# PM_proto_2.net
KiCad netlist of a schematic drawn in EAGLE
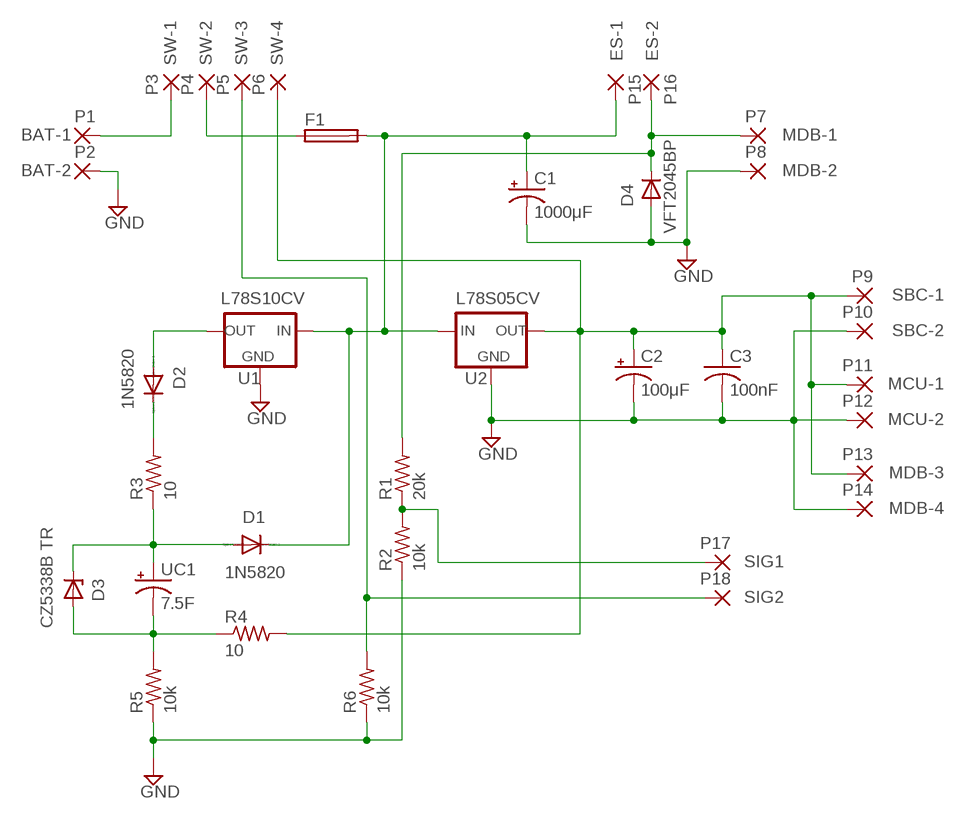
[diagram p0: schematic, sheet 1]

(export (version "E")
  (design (tool "Eeschema 10.0.6"))
  (components
    (comp (ref "C1")
      (value "1000μF")
      (footprint "eagle-import:E7,5-16")
      (libsource (lib "eagle-import") (part "CPOL-USE7.5-16"))
    )
    (comp (ref "C2")
      (value "100μF")
      (footprint "eagle-import:E2,5-6E")
      (libsource (lib "eagle-import") (part "CPOL-USE2,5-6E"))
    )
    (comp (ref "C3")
      (value "100nF")
      (footprint "eagle-import:C050-024X044")
      (libsource (lib "eagle-import") (part "C-US050-024X044"))
    )
    (comp (ref "D1")
      (value "1N5820")
      (footprint "eagle-import:DO41-10")
      (libsource (lib "eagle-import") (part "1N4004"))
    )
    (comp (ref "D2")
      (value "1N5820")
      (footprint "eagle-import:DO41-10")
      (libsource (lib "eagle-import") (part "1N4004"))
    )
    (comp (ref "D3")
      (value "CZ5338B TR")
      (footprint "eagle-import:DO41Z10")
      (libsource (lib "eagle-import") (part "1N4728"))
    )
    (comp (ref "D4")
      (value "VFT2045BP")
      (footprint "eagle-import:VFT2045BP")
      (libsource (lib "eagle-import") (part "VFT2045BP"))
    )
    (comp (ref "F1")
      (value "0297015FUSE")
      (footprint "eagle-import:0297015HOLDER")
      (libsource (lib "eagle-import") (part "0297015FUSE"))
    )
    (comp (ref "P1")
      (value "BAT-1")
      (footprint "eagle-import:1,6_0,8")
      (libsource (lib "eagle-import") (part "1,6/0,8"))
    )
    (comp (ref "P2")
      (value "BAT-2")
      (footprint "eagle-import:1,6_0,8")
      (libsource (lib "eagle-import") (part "1,6/0,8"))
    )
    (comp (ref "P3")
      (value "SW-1")
      (footprint "eagle-import:1,6_0,8")
      (libsource (lib "eagle-import") (part "1,6/0,8"))
    )
    (comp (ref "P4")
      (value "SW-2")
      (footprint "eagle-import:1,6_0,8")
      (libsource (lib "eagle-import") (part "1,6/0,8"))
    )
    (comp (ref "P5")
      (value "SW-3")
      (footprint "eagle-import:1,6_0,8")
      (libsource (lib "eagle-import") (part "1,6/0,8"))
    )
    (comp (ref "P6")
      (value "SW-4")
      (footprint "eagle-import:1,6_0,8")
      (libsource (lib "eagle-import") (part "1,6/0,8"))
    )
    (comp (ref "P7")
      (value "MDB-1")
      (footprint "eagle-import:1,6_0,8")
      (libsource (lib "eagle-import") (part "1,6/0,8"))
    )
    (comp (ref "P8")
      (value "MDB-2")
      (footprint "eagle-import:1,6_0,8")
      (libsource (lib "eagle-import") (part "1,6/0,8"))
    )
    (comp (ref "P9")
      (value "SBC-1")
      (footprint "eagle-import:1,6_0,8")
      (libsource (lib "eagle-import") (part "1,6/0,8"))
    )
    (comp (ref "P10")
      (value "SBC-2")
      (footprint "eagle-import:1,6_0,8")
      (libsource (lib "eagle-import") (part "1,6/0,8"))
    )
    (comp (ref "P11")
      (value "MCU-1")
      (footprint "eagle-import:1,6_0,8")
      (libsource (lib "eagle-import") (part "1,6/0,8"))
    )
    (comp (ref "P12")
      (value "MCU-2")
      (footprint "eagle-import:1,6_0,8")
      (libsource (lib "eagle-import") (part "1,6/0,8"))
    )
    (comp (ref "P13")
      (value "MDB-3")
      (footprint "eagle-import:1,6_0,8")
      (libsource (lib "eagle-import") (part "1,6/0,8"))
    )
    (comp (ref "P14")
      (value "MDB-4")
      (footprint "eagle-import:1,6_0,8")
      (libsource (lib "eagle-import") (part "1,6/0,8"))
    )
    (comp (ref "P15")
      (value "ES-1")
      (footprint "eagle-import:1,6_0,8")
      (libsource (lib "eagle-import") (part "1,6/0,8"))
    )
    (comp (ref "P16")
      (value "ES-2")
      (footprint "eagle-import:1,6_0,8")
      (libsource (lib "eagle-import") (part "1,6/0,8"))
    )
    (comp (ref "P17")
      (value "SIG1")
      (footprint "eagle-import:1,6_0,8")
      (libsource (lib "eagle-import") (part "1,6/0,8"))
    )
    (comp (ref "P18")
      (value "SIG2")
      (footprint "eagle-import:1,6_0,8")
      (libsource (lib "eagle-import") (part "1,6/0,8"))
    )
    (comp (ref "R1")
      (value "20k")
      (footprint "eagle-import:0204_7")
      (libsource (lib "eagle-import") (part "R-US_0204/7"))
    )
    (comp (ref "R2")
      (value "10k")
      (footprint "eagle-import:0204_7")
      (libsource (lib "eagle-import") (part "R-US_0204/7"))
    )
    (comp (ref "R3")
      (value "10")
      (footprint "eagle-import:TNP10SC10R0FE")
      (libsource (lib "eagle-import") (part "TNP10SC10R0FE"))
    )
    (comp (ref "R4")
      (value "10")
      (footprint "eagle-import:TNP10SC10R0FE")
      (libsource (lib "eagle-import") (part "TNP10SC10R0FE"))
    )
    (comp (ref "R5")
      (value "10k")
      (footprint "eagle-import:0204_7")
      (libsource (lib "eagle-import") (part "R-US_0204/7"))
    )
    (comp (ref "R6")
      (value "10k")
      (footprint "eagle-import:0204_7")
      (libsource (lib "eagle-import") (part "R-US_0204/7"))
    )
    (comp (ref "U1")
      (value "L78S10CV")
      (footprint "eagle-import:78XXS")
      (libsource (lib "eagle-import") (part "78XXS"))
    )
    (comp (ref "U2")
      (value "L78S05CV")
      (footprint "eagle-import:78XXS")
      (fields (field (name "SPICEPREFIX") "J"))
      (libsource (lib "eagle-import") (part "78XXS"))
    )
    (comp (ref "UC1")
      (value "7.5F")
      (footprint "eagle-import:SCMT32D755MRBB0")
      (libsource (lib "eagle-import") (part "SCMT32D755MRBB0"))
    )
  )
  (nets
    (net (code "1") (name "GND") (class "Default")
      (node (ref "C1") (pin "-") (pinfunction "-_-") (pintype "passive"))
      (node (ref "C2") (pin "-") (pinfunction "-_-") (pintype "passive"))
      (node (ref "C3") (pin "2") (pinfunction "2_2") (pintype "passive"))
      (node (ref "D4") (pin "2") (pinfunction "A_2") (pintype "passive"))
      (node (ref "P10") (pin "1") (pinfunction "P_1") (pintype "passive"))
      (node (ref "P12") (pin "1") (pinfunction "P_1") (pintype "passive"))
      (node (ref "P14") (pin "1") (pinfunction "P_1") (pintype "passive"))
      (node (ref "P2") (pin "1") (pinfunction "P_1") (pintype "passive"))
      (node (ref "P8") (pin "1") (pinfunction "P_1") (pintype "passive"))
      (node (ref "R2") (pin "1") (pinfunction "1_1") (pintype "passive"))
      (node (ref "R5") (pin "1") (pinfunction "1_1") (pintype "passive"))
      (node (ref "R6") (pin "1") (pinfunction "1_1") (pintype "passive"))
      (node (ref "U1") (pin "GND") (pinfunction "GND_GND") (pintype "input"))
      (node (ref "U2") (pin "GND") (pinfunction "GND_GND") (pintype "input"))
    )
    (net (code "2") (name "Net-(D2-PadA)") (class "Default")
      (node (ref "D2") (pin "A") (pinfunction "A_A") (pintype "passive"))
      (node (ref "U1") (pin "OUT") (pinfunction "OUT_OUT") (pintype "passive"))
    )
    (net (code "3") (name "Net-(D2-PadC)") (class "Default")
      (node (ref "D2") (pin "C") (pinfunction "C_C") (pintype "passive"))
      (node (ref "R3") (pin "2") (pinfunction "2_2") (pintype "passive"))
    )
    (net (code "4") (name "Net-(D4-C)") (class "Default")
      (node (ref "D4") (pin "1") (pinfunction "C_1") (pintype "passive"))
      (node (ref "P16") (pin "1") (pinfunction "P_1") (pintype "passive"))
      (node (ref "P7") (pin "1") (pinfunction "P_1") (pintype "passive"))
      (node (ref "R1") (pin "2") (pinfunction "2_2") (pintype "passive"))
    )
    (net (code "5") (name "Net-(P1-P)") (class "Default")
      (node (ref "P1") (pin "1") (pinfunction "P_1") (pintype "passive"))
      (node (ref "P3") (pin "1") (pinfunction "P_1") (pintype "passive"))
    )
    (net (code "6") (name "Net-(P4-P)") (class "Default")
      (node (ref "F1") (pin "1") (pinfunction "1_1") (pintype "passive"))
      (node (ref "F1") (pin "2") (pinfunction "1_2") (pintype "passive"))
      (node (ref "P4") (pin "1") (pinfunction "P_1") (pintype "passive"))
    )
    (net (code "7") (name "Net-(P11-P)") (class "Default")
      (node (ref "C2") (pin "+") (pinfunction "+_+") (pintype "passive"))
      (node (ref "C3") (pin "1") (pinfunction "1_1") (pintype "passive"))
      (node (ref "P11") (pin "1") (pinfunction "P_1") (pintype "passive"))
      (node (ref "P13") (pin "1") (pinfunction "P_1") (pintype "passive"))
      (node (ref "P6") (pin "1") (pinfunction "P_1") (pintype "passive"))
      (node (ref "P9") (pin "1") (pinfunction "P_1") (pintype "passive"))
      (node (ref "R4") (pin "2") (pinfunction "2_2") (pintype "passive"))
      (node (ref "U2") (pin "OUT") (pinfunction "OUT_OUT") (pintype "passive"))
    )
    (net (code "8") (name "Net-(P15-P)") (class "Default")
      (node (ref "C1") (pin "+") (pinfunction "+_+") (pintype "passive"))
      (node (ref "D1") (pin "C") (pinfunction "C_C") (pintype "passive"))
      (node (ref "F1") (pin "3") (pinfunction "2_3") (pintype "passive"))
      (node (ref "F1") (pin "4") (pinfunction "2_4") (pintype "passive"))
      (node (ref "P15") (pin "1") (pinfunction "P_1") (pintype "passive"))
      (node (ref "U1") (pin "IN") (pinfunction "IN_IN") (pintype "input"))
      (node (ref "U2") (pin "IN") (pinfunction "IN_IN") (pintype "input"))
    )
    (net (code "9") (name "Net-(P17-P)") (class "Default")
      (node (ref "P17") (pin "1") (pinfunction "P_1") (pintype "passive"))
      (node (ref "R1") (pin "1") (pinfunction "1_1") (pintype "passive"))
      (node (ref "R2") (pin "2") (pinfunction "2_2") (pintype "passive"))
    )
    (net (code "10") (name "Net-(P18-P)") (class "Default")
      (node (ref "P18") (pin "1") (pinfunction "P_1") (pintype "passive"))
      (node (ref "P5") (pin "1") (pinfunction "P_1") (pintype "passive"))
      (node (ref "R6") (pin "2") (pinfunction "2_2") (pintype "passive"))
    )
    (net (code "11") (name "Net-(UC1-+)") (class "Default")
      (node (ref "D1") (pin "A") (pinfunction "A_A") (pintype "passive"))
      (node (ref "D3") (pin "C") (pinfunction "C_C") (pintype "passive"))
      (node (ref "R3") (pin "1") (pinfunction "1_1") (pintype "passive"))
      (node (ref "UC1") (pin "1") (pinfunction "+_1") (pintype "passive"))
    )
    (net (code "12") (name "Net-(UC1--)") (class "Default")
      (node (ref "D3") (pin "A") (pinfunction "A_A") (pintype "passive"))
      (node (ref "R4") (pin "1") (pinfunction "1_1") (pintype "passive"))
      (node (ref "R5") (pin "2") (pinfunction "2_2") (pintype "passive"))
      (node (ref "UC1") (pin "2") (pinfunction "-_2") (pintype "passive"))
    )
  )
)
